# enrgymeter_-_Copy.net
KiCad netlist of a schematic drawn in EAGLE
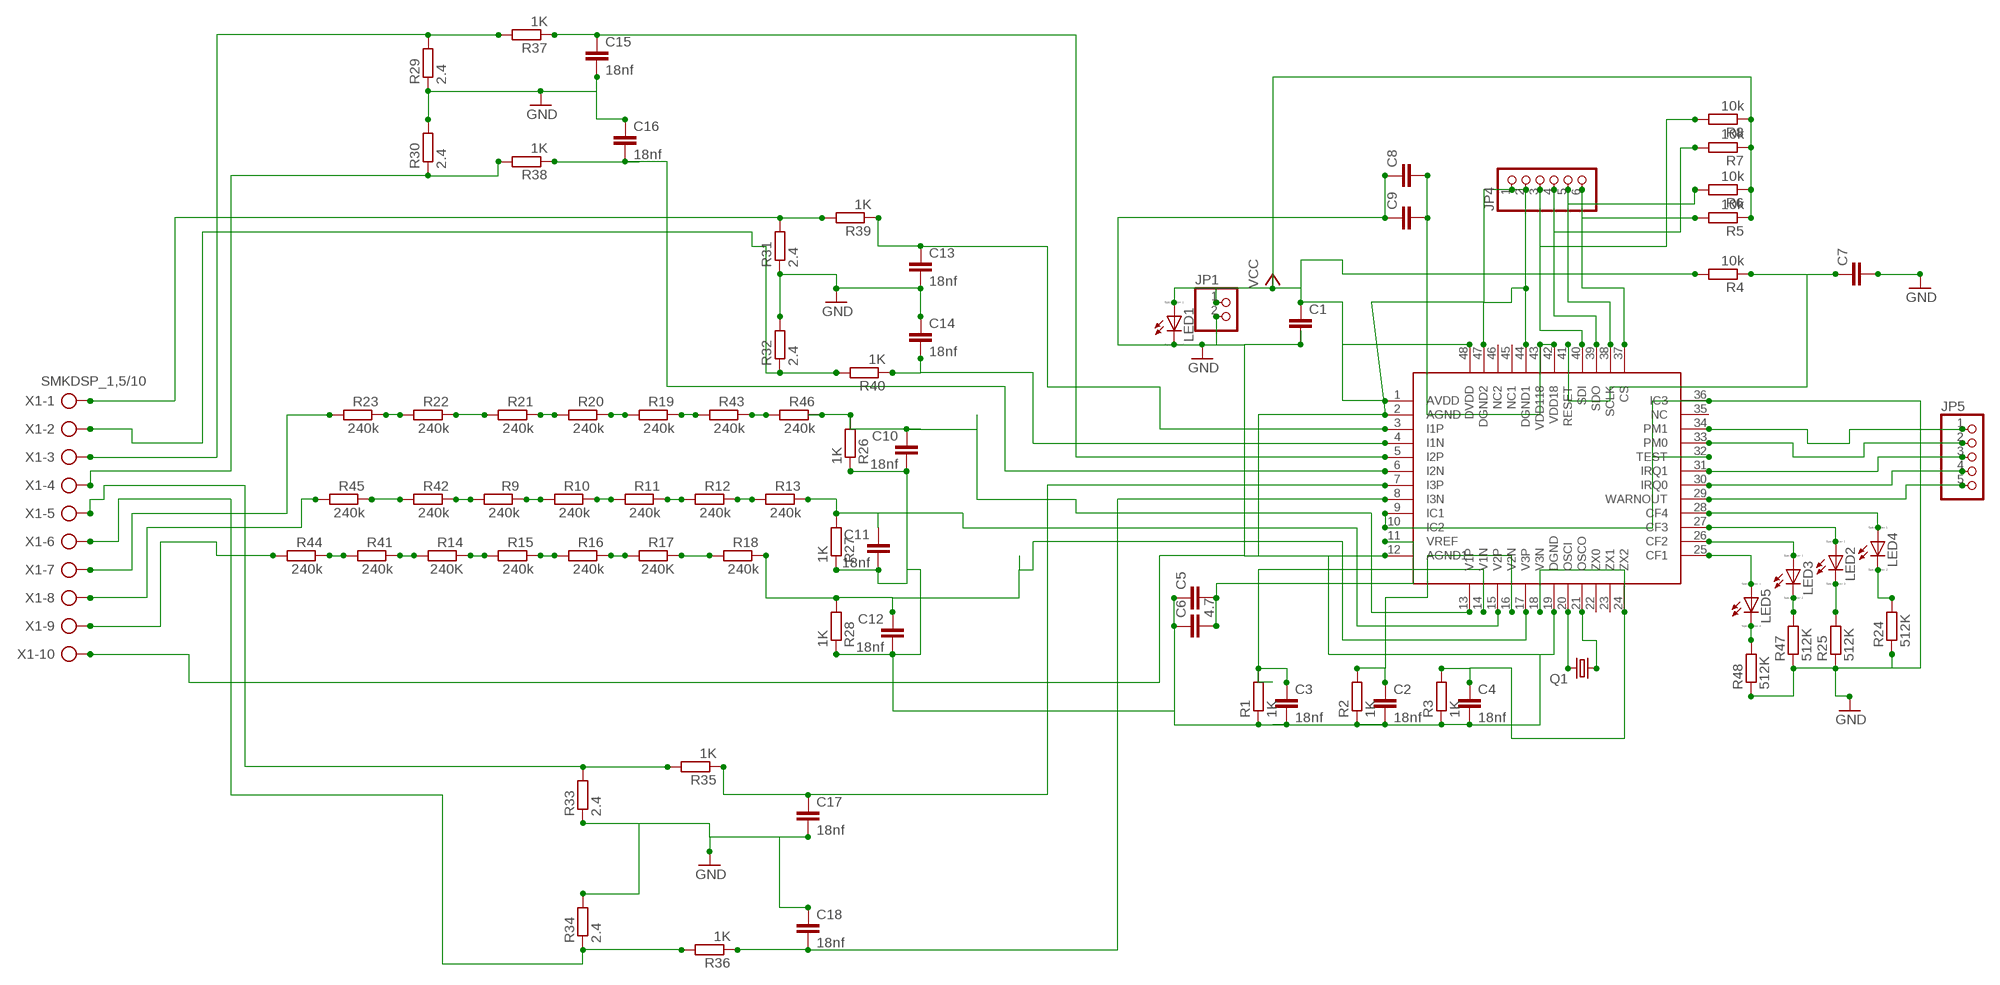
[diagram p0: schematic, sheet 1]

(export (version "E")
  (design (tool "Eeschema 10.0.6"))
  (components
    (comp (ref "C1")
      (value "C-EUC1210")
      (footprint "eagle-import:C1210")
      (libsource (lib "eagle-import") (part "C-EUC1210"))
    )
    (comp (ref "C2")
      (value "18nf")
      (footprint "eagle-import:C0402")
      (libsource (lib "eagle-import") (part "C-EUC0402"))
    )
    (comp (ref "C3")
      (value "18nf")
      (footprint "eagle-import:C0402")
      (libsource (lib "eagle-import") (part "C-EUC0402"))
    )
    (comp (ref "C4")
      (value "18nf")
      (footprint "eagle-import:C0402")
      (libsource (lib "eagle-import") (part "C-EUC0402"))
    )
    (comp (ref "C5")
      (value "C-EUC1210")
      (footprint "eagle-import:C1210")
      (libsource (lib "eagle-import") (part "C-EUC1210"))
    )
    (comp (ref "C6")
      (value "4.7")
      (footprint "eagle-import:C0805")
      (libsource (lib "eagle-import") (part "C-EUC0805"))
    )
    (comp (ref "C7")
      (value "C-EUC1210")
      (footprint "eagle-import:C1210")
      (libsource (lib "eagle-import") (part "C-EUC1210"))
    )
    (comp (ref "C8")
      (value "C-EUC1210")
      (footprint "eagle-import:C1210")
      (libsource (lib "eagle-import") (part "C-EUC1210"))
    )
    (comp (ref "C9")
      (value "C-EUC1210")
      (footprint "eagle-import:C1210")
      (libsource (lib "eagle-import") (part "C-EUC1210"))
    )
    (comp (ref "C10")
      (value "18nf")
      (footprint "eagle-import:C0402")
      (libsource (lib "eagle-import") (part "C-EUC0402"))
    )
    (comp (ref "C11")
      (value "18nf")
      (footprint "eagle-import:C0402")
      (libsource (lib "eagle-import") (part "C-EUC0402"))
    )
    (comp (ref "C12")
      (value "18nf")
      (footprint "eagle-import:C0402")
      (libsource (lib "eagle-import") (part "C-EUC0402"))
    )
    (comp (ref "C13")
      (value "18nf")
      (footprint "eagle-import:C0402")
      (libsource (lib "eagle-import") (part "C-EUC0402"))
    )
    (comp (ref "C14")
      (value "18nf")
      (footprint "eagle-import:C0402")
      (libsource (lib "eagle-import") (part "C-EUC0402"))
    )
    (comp (ref "C15")
      (value "18nf")
      (footprint "eagle-import:C0402")
      (libsource (lib "eagle-import") (part "C-EUC0402"))
    )
    (comp (ref "C16")
      (value "18nf")
      (footprint "eagle-import:C0402")
      (libsource (lib "eagle-import") (part "C-EUC0402"))
    )
    (comp (ref "C17")
      (value "18nf")
      (footprint "eagle-import:C0402")
      (libsource (lib "eagle-import") (part "C-EUC0402"))
    )
    (comp (ref "C18")
      (value "18nf")
      (footprint "eagle-import:C0402")
      (libsource (lib "eagle-import") (part "C-EUC0402"))
    )
    (comp (ref "JP1")
      (value "PINHD-1X2_2.54-SMD-90°")
      (footprint "eagle-import:1X02SMD_90")
      (libsource (lib "eagle-import") (part "PINHD-1X2_2.54-SMD-90°"))
    )
    (comp (ref "JP4")
      (value "PINHD-1X6_2.54-SMD-90°")
      (footprint "eagle-import:1X06SMD_90")
      (libsource (lib "eagle-import") (part "PINHD-1X6_2.54-SMD-90°"))
    )
    (comp (ref "JP5")
      (value "PINHD-1X5_2.54-SMD-90°")
      (footprint "eagle-import:1X05SMD_90")
      (libsource (lib "eagle-import") (part "PINHD-1X5_2.54-SMD-90°"))
    )
    (comp (ref "LED1")
      (value "LED_E")
      (footprint "eagle-import:LED_1206")
      (libsource (lib "eagle-import") (part "LED_E"))
    )
    (comp (ref "LED2")
      (value "LED_E")
      (footprint "eagle-import:LED_1206")
      (libsource (lib "eagle-import") (part "LED_E"))
    )
    (comp (ref "LED3")
      (value "LED_E")
      (footprint "eagle-import:LED_1206")
      (libsource (lib "eagle-import") (part "LED_E"))
    )
    (comp (ref "LED4")
      (value "LED_E")
      (footprint "eagle-import:LED_1206")
      (libsource (lib "eagle-import") (part "LED_E"))
    )
    (comp (ref "LED5")
      (value "LED_E")
      (footprint "eagle-import:LED_1206")
      (libsource (lib "eagle-import") (part "LED_E"))
    )
    (comp (ref "Q1")
      (value "CRYSTALSM49")
      (footprint "eagle-import:SM49")
      (libsource (lib "eagle-import") (part "CRYSTALSM49"))
    )
    (comp (ref "R1")
      (value "1K")
      (footprint "eagle-import:R2512")
      (libsource (lib "eagle-import") (part "R-EU_R2512"))
    )
    (comp (ref "R2")
      (value "1K")
      (footprint "eagle-import:R2512")
      (libsource (lib "eagle-import") (part "R-EU_R2512"))
    )
    (comp (ref "R3")
      (value "1K")
      (footprint "eagle-import:R2512")
      (libsource (lib "eagle-import") (part "R-EU_R2512"))
    )
    (comp (ref "R4")
      (value "10k")
      (footprint "eagle-import:R2512")
      (libsource (lib "eagle-import") (part "R-EU_R2512"))
    )
    (comp (ref "R5")
      (value "10k")
      (footprint "eagle-import:R2512")
      (libsource (lib "eagle-import") (part "R-EU_R2512"))
    )
    (comp (ref "R6")
      (value "10k")
      (footprint "eagle-import:R2512")
      (libsource (lib "eagle-import") (part "R-EU_R2512"))
    )
    (comp (ref "R7")
      (value "10k")
      (footprint "eagle-import:R2512")
      (libsource (lib "eagle-import") (part "R-EU_R2512"))
    )
    (comp (ref "R8")
      (value "10k")
      (footprint "eagle-import:R2512")
      (libsource (lib "eagle-import") (part "R-EU_R2512"))
    )
    (comp (ref "R9")
      (value "240k")
      (footprint "eagle-import:R2512W")
      (libsource (lib "eagle-import") (part "R-EU_R2512W"))
    )
    (comp (ref "R10")
      (value "240k")
      (footprint "eagle-import:R2512W")
      (libsource (lib "eagle-import") (part "R-EU_R2512W"))
    )
    (comp (ref "R11")
      (value "240k")
      (footprint "eagle-import:R2512W")
      (libsource (lib "eagle-import") (part "R-EU_R2512W"))
    )
    (comp (ref "R12")
      (value "240k")
      (footprint "eagle-import:R2512W")
      (libsource (lib "eagle-import") (part "R-EU_R2512W"))
    )
    (comp (ref "R13")
      (value "240k")
      (footprint "eagle-import:R2512W")
      (libsource (lib "eagle-import") (part "R-EU_R2512W"))
    )
    (comp (ref "R14")
      (value "240K")
      (footprint "eagle-import:R2512W")
      (libsource (lib "eagle-import") (part "R-EU_R2512W"))
    )
    (comp (ref "R15")
      (value "240k")
      (footprint "eagle-import:R2512W")
      (libsource (lib "eagle-import") (part "R-EU_R2512W"))
    )
    (comp (ref "R16")
      (value "240k")
      (footprint "eagle-import:R2512W")
      (libsource (lib "eagle-import") (part "R-EU_R2512W"))
    )
    (comp (ref "R17")
      (value "240K")
      (footprint "eagle-import:R2512W")
      (libsource (lib "eagle-import") (part "R-EU_R2512W"))
    )
    (comp (ref "R18")
      (value "240k")
      (footprint "eagle-import:R2512W")
      (libsource (lib "eagle-import") (part "R-EU_R2512W"))
    )
    (comp (ref "R19")
      (value "240k")
      (footprint "eagle-import:R2512W")
      (libsource (lib "eagle-import") (part "R-EU_R2512W"))
    )
    (comp (ref "R20")
      (value "240k")
      (footprint "eagle-import:R2512W")
      (libsource (lib "eagle-import") (part "R-EU_R2512W"))
    )
    (comp (ref "R21")
      (value "240k")
      (footprint "eagle-import:R2512W")
      (libsource (lib "eagle-import") (part "R-EU_R2512W"))
    )
    (comp (ref "R22")
      (value "240k")
      (footprint "eagle-import:R2512W")
      (libsource (lib "eagle-import") (part "R-EU_R2512W"))
    )
    (comp (ref "R23")
      (value "240k")
      (footprint "eagle-import:R2512W")
      (libsource (lib "eagle-import") (part "R-EU_R2512W"))
    )
    (comp (ref "R24")
      (value "512K")
      (footprint "eagle-import:R2512W")
      (libsource (lib "eagle-import") (part "R-EU_R2512W"))
    )
    (comp (ref "R25")
      (value "512K")
      (footprint "eagle-import:R2512W")
      (libsource (lib "eagle-import") (part "R-EU_R2512W"))
    )
    (comp (ref "R26")
      (value "1K")
      (footprint "eagle-import:R2512")
      (libsource (lib "eagle-import") (part "R-EU_R2512"))
    )
    (comp (ref "R27")
      (value "1K")
      (footprint "eagle-import:R2512")
      (libsource (lib "eagle-import") (part "R-EU_R2512"))
    )
    (comp (ref "R28")
      (value "1K")
      (footprint "eagle-import:R2512")
      (libsource (lib "eagle-import") (part "R-EU_R2512"))
    )
    (comp (ref "R29")
      (value "2.4")
      (footprint "eagle-import:R2512")
      (libsource (lib "eagle-import") (part "R-EU_R2512"))
    )
    (comp (ref "R30")
      (value "2.4")
      (footprint "eagle-import:R2512")
      (libsource (lib "eagle-import") (part "R-EU_R2512"))
    )
    (comp (ref "R31")
      (value "2.4")
      (footprint "eagle-import:R2512")
      (libsource (lib "eagle-import") (part "R-EU_R2512"))
    )
    (comp (ref "R32")
      (value "2.4")
      (footprint "eagle-import:R2512")
      (libsource (lib "eagle-import") (part "R-EU_R2512"))
    )
    (comp (ref "R33")
      (value "2.4")
      (footprint "eagle-import:R2512")
      (libsource (lib "eagle-import") (part "R-EU_R2512"))
    )
    (comp (ref "R34")
      (value "2.4")
      (footprint "eagle-import:R2512")
      (libsource (lib "eagle-import") (part "R-EU_R2512"))
    )
    (comp (ref "R35")
      (value "1K")
      (footprint "eagle-import:R2512")
      (libsource (lib "eagle-import") (part "R-EU_R2512"))
    )
    (comp (ref "R36")
      (value "1K")
      (footprint "eagle-import:R2512")
      (libsource (lib "eagle-import") (part "R-EU_R2512"))
    )
    (comp (ref "R37")
      (value "1K")
      (footprint "eagle-import:R2512")
      (libsource (lib "eagle-import") (part "R-EU_R2512"))
    )
    (comp (ref "R38")
      (value "1K")
      (footprint "eagle-import:R2512")
      (libsource (lib "eagle-import") (part "R-EU_R2512"))
    )
    (comp (ref "R39")
      (value "1K")
      (footprint "eagle-import:R2512")
      (libsource (lib "eagle-import") (part "R-EU_R2512"))
    )
    (comp (ref "R40")
      (value "1K")
      (footprint "eagle-import:R2512")
      (libsource (lib "eagle-import") (part "R-EU_R2512"))
    )
    (comp (ref "R41")
      (value "240k")
      (footprint "eagle-import:R2512W")
      (libsource (lib "eagle-import") (part "R-EU_R2512W"))
    )
    (comp (ref "R42")
      (value "240k")
      (footprint "eagle-import:R2512W")
      (libsource (lib "eagle-import") (part "R-EU_R2512W"))
    )
    (comp (ref "R43")
      (value "240k")
      (footprint "eagle-import:R2512W")
      (libsource (lib "eagle-import") (part "R-EU_R2512W"))
    )
    (comp (ref "R44")
      (value "240k")
      (footprint "eagle-import:R2512W")
      (libsource (lib "eagle-import") (part "R-EU_R2512W"))
    )
    (comp (ref "R45")
      (value "240k")
      (footprint "eagle-import:R2512W")
      (libsource (lib "eagle-import") (part "R-EU_R2512W"))
    )
    (comp (ref "R46")
      (value "240k")
      (footprint "eagle-import:R2512W")
      (libsource (lib "eagle-import") (part "R-EU_R2512W"))
    )
    (comp (ref "R47")
      (value "512K")
      (footprint "eagle-import:R2512W")
      (libsource (lib "eagle-import") (part "R-EU_R2512W"))
    )
    (comp (ref "R48")
      (value "512K")
      (footprint "eagle-import:R2512W")
      (libsource (lib "eagle-import") (part "R-EU_R2512W"))
    )
    (comp (ref "U$1")
      (value "M90E32AS")
      (footprint "eagle-import:M90E32AS")
      (libsource (lib "eagle-import") (part "M90E32AS"))
    )
    (comp (ref "X1")
      (value "SMKDSP_1,5/10")
      (footprint "eagle-import:SMKDSP_1,5_10")
      (fields (field (name "MF") "FARNELL") (field (name "MPN") "1733651"))
      (libsource (lib "eagle-import") (part "SMKDSP_1,5/10"))
    )
  )
  (nets
    (net (code "1") (name "GND") (class "Default")
      (node (ref "C1") (pin "2") (pinfunction "2_2") (pintype "passive"))
      (node (ref "C10") (pin "2") (pinfunction "2_2") (pintype "passive"))
      (node (ref "C11") (pin "2") (pinfunction "2_2") (pintype "passive"))
      (node (ref "C12") (pin "2") (pinfunction "2_2") (pintype "passive"))
      (node (ref "C13") (pin "2") (pinfunction "2_2") (pintype "passive"))
      (node (ref "C14") (pin "1") (pinfunction "1_1") (pintype "passive"))
      (node (ref "C15") (pin "2") (pinfunction "2_2") (pintype "passive"))
      (node (ref "C16") (pin "1") (pinfunction "1_1") (pintype "passive"))
      (node (ref "C17") (pin "2") (pinfunction "2_2") (pintype "passive"))
      (node (ref "C18") (pin "1") (pinfunction "1_1") (pintype "passive"))
      (node (ref "C2") (pin "2") (pinfunction "2_2") (pintype "passive"))
      (node (ref "C3") (pin "2") (pinfunction "2_2") (pintype "passive"))
      (node (ref "C4") (pin "2") (pinfunction "2_2") (pintype "passive"))
      (node (ref "C5") (pin "1") (pinfunction "1_1") (pintype "passive"))
      (node (ref "C6") (pin "1") (pinfunction "1_1") (pintype "passive"))
      (node (ref "C7") (pin "2") (pinfunction "2_2") (pintype "passive"))
      (node (ref "C8") (pin "1") (pinfunction "1_1") (pintype "passive"))
      (node (ref "C9") (pin "1") (pinfunction "1_1") (pintype "passive"))
      (node (ref "JP1") (pin "2") (pinfunction "2_2") (pintype "passive"))
      (node (ref "JP4") (pin "1") (pinfunction "1_1") (pintype "passive"))
      (node (ref "JP4") (pin "2") (pinfunction "2_2") (pintype "passive"))
      (node (ref "LED1") (pin "C") (pinfunction "C_C") (pintype "passive"))
      (node (ref "R1") (pin "1") (pinfunction "1_1") (pintype "passive"))
      (node (ref "R2") (pin "1") (pinfunction "1_1") (pintype "passive"))
      (node (ref "R24") (pin "1") (pinfunction "1_1") (pintype "passive"))
      (node (ref "R25") (pin "1") (pinfunction "1_1") (pintype "passive"))
      (node (ref "R26") (pin "1") (pinfunction "1_1") (pintype "passive"))
      (node (ref "R27") (pin "1") (pinfunction "1_1") (pintype "passive"))
      (node (ref "R28") (pin "1") (pinfunction "1_1") (pintype "passive"))
      (node (ref "R29") (pin "1") (pinfunction "1_1") (pintype "passive"))
      (node (ref "R3") (pin "1") (pinfunction "1_1") (pintype "passive"))
      (node (ref "R30") (pin "2") (pinfunction "2_2") (pintype "passive"))
      (node (ref "R31") (pin "1") (pinfunction "1_1") (pintype "passive"))
      (node (ref "R32") (pin "2") (pinfunction "2_2") (pintype "passive"))
      (node (ref "R33") (pin "1") (pinfunction "1_1") (pintype "passive"))
      (node (ref "R34") (pin "2") (pinfunction "2_2") (pintype "passive"))
      (node (ref "R47") (pin "1") (pinfunction "1_1") (pintype "passive"))
      (node (ref "R48") (pin "1") (pinfunction "1_1") (pintype "passive"))
      (node (ref "U$1") (pin "10") (pinfunction "IC2_10") (pintype "bidirectional"))
      (node (ref "U$1") (pin "12") (pinfunction "AGND1_12") (pintype "bidirectional"))
      (node (ref "U$1") (pin "19") (pinfunction "DGND_19") (pintype "bidirectional"))
      (node (ref "U$1") (pin "2") (pinfunction "AGND_2") (pintype "bidirectional"))
      (node (ref "U$1") (pin "32") (pinfunction "TEST_32") (pintype "bidirectional"))
      (node (ref "U$1") (pin "36") (pinfunction "IC3_36") (pintype "bidirectional"))
      (node (ref "U$1") (pin "44") (pinfunction "DGND1_44") (pintype "bidirectional"))
      (node (ref "U$1") (pin "47") (pinfunction "DGND2_47") (pintype "bidirectional"))
      (node (ref "U$1") (pin "9") (pinfunction "IC1_9") (pintype "bidirectional"))
      (node (ref "X1") (pin "10") (pinfunction "KL_10") (pintype "passive"))
    )
    (net (code "2") (name "Net-(LED2-PadC)") (class "Default")
      (node (ref "LED2") (pin "C") (pinfunction "C_C") (pintype "passive"))
      (node (ref "R25") (pin "2") (pinfunction "2_2") (pintype "passive"))
    )
    (net (code "3") (name "Net-(LED3-PadC)") (class "Default")
      (node (ref "LED3") (pin "C") (pinfunction "C_C") (pintype "passive"))
      (node (ref "R47") (pin "2") (pinfunction "2_2") (pintype "passive"))
    )
    (net (code "4") (name "Net-(LED4-PadC)") (class "Default")
      (node (ref "LED4") (pin "C") (pinfunction "C_C") (pintype "passive"))
      (node (ref "R24") (pin "2") (pinfunction "2_2") (pintype "passive"))
    )
    (net (code "5") (name "Net-(LED5-PadC)") (class "Default")
      (node (ref "LED5") (pin "C") (pinfunction "C_C") (pintype "passive"))
      (node (ref "R48") (pin "2") (pinfunction "2_2") (pintype "passive"))
    )
    (net (code "6") (name "Net-(R10-Pad1)") (class "Default")
      (node (ref "R10") (pin "1") (pinfunction "1_1") (pintype "passive"))
      (node (ref "R11") (pin "2") (pinfunction "2_2") (pintype "passive"))
    )
    (net (code "7") (name "Net-(R10-Pad2)") (class "Default")
      (node (ref "R10") (pin "2") (pinfunction "2_2") (pintype "passive"))
      (node (ref "R9") (pin "1") (pinfunction "1_1") (pintype "passive"))
    )
    (net (code "8") (name "Net-(R11-Pad1)") (class "Default")
      (node (ref "R11") (pin "1") (pinfunction "1_1") (pintype "passive"))
      (node (ref "R12") (pin "2") (pinfunction "2_2") (pintype "passive"))
    )
    (net (code "9") (name "Net-(R12-Pad1)") (class "Default")
      (node (ref "R12") (pin "1") (pinfunction "1_1") (pintype "passive"))
      (node (ref "R13") (pin "2") (pinfunction "2_2") (pintype "passive"))
    )
    (net (code "10") (name "Net-(R14-Pad1)") (class "Default")
      (node (ref "R14") (pin "1") (pinfunction "1_1") (pintype "passive"))
      (node (ref "R15") (pin "2") (pinfunction "2_2") (pintype "passive"))
    )
    (net (code "11") (name "Net-(R14-Pad2)") (class "Default")
      (node (ref "R14") (pin "2") (pinfunction "2_2") (pintype "passive"))
      (node (ref "R41") (pin "1") (pinfunction "1_1") (pintype "passive"))
    )
    (net (code "12") (name "Net-(R15-Pad1)") (class "Default")
      (node (ref "R15") (pin "1") (pinfunction "1_1") (pintype "passive"))
      (node (ref "R16") (pin "2") (pinfunction "2_2") (pintype "passive"))
    )
    (net (code "13") (name "Net-(R16-Pad1)") (class "Default")
      (node (ref "R16") (pin "1") (pinfunction "1_1") (pintype "passive"))
      (node (ref "R17") (pin "2") (pinfunction "2_2") (pintype "passive"))
    )
    (net (code "14") (name "Net-(R17-Pad1)") (class "Default")
      (node (ref "R17") (pin "1") (pinfunction "1_1") (pintype "passive"))
      (node (ref "R18") (pin "2") (pinfunction "2_2") (pintype "passive"))
    )
    (net (code "15") (name "Net-(R19-Pad1)") (class "Default")
      (node (ref "R19") (pin "1") (pinfunction "1_1") (pintype "passive"))
      (node (ref "R43") (pin "2") (pinfunction "2_2") (pintype "passive"))
    )
    (net (code "16") (name "Net-(R19-Pad2)") (class "Default")
      (node (ref "R19") (pin "2") (pinfunction "2_2") (pintype "passive"))
      (node (ref "R20") (pin "1") (pinfunction "1_1") (pintype "passive"))
    )
    (net (code "17") (name "Net-(R20-Pad2)") (class "Default")
      (node (ref "R20") (pin "2") (pinfunction "2_2") (pintype "passive"))
      (node (ref "R21") (pin "1") (pinfunction "1_1") (pintype "passive"))
    )
    (net (code "18") (name "Net-(R21-Pad2)") (class "Default")
      (node (ref "R21") (pin "2") (pinfunction "2_2") (pintype "passive"))
      (node (ref "R22") (pin "1") (pinfunction "1_1") (pintype "passive"))
    )
    (net (code "19") (name "Net-(R22-Pad2)") (class "Default")
      (node (ref "R22") (pin "2") (pinfunction "2_2") (pintype "passive"))
      (node (ref "R23") (pin "1") (pinfunction "1_1") (pintype "passive"))
    )
    (net (code "20") (name "Net-(R41-Pad2)") (class "Default")
      (node (ref "R41") (pin "2") (pinfunction "2_2") (pintype "passive"))
      (node (ref "R44") (pin "1") (pinfunction "1_1") (pintype "passive"))
    )
    (net (code "21") (name "Net-(R42-Pad1)") (class "Default")
      (node (ref "R42") (pin "1") (pinfunction "1_1") (pintype "passive"))
      (node (ref "R9") (pin "2") (pinfunction "2_2") (pintype "passive"))
    )
    (net (code "22") (name "Net-(R42-Pad2)") (class "Default")
      (node (ref "R42") (pin "2") (pinfunction "2_2") (pintype "passive"))
      (node (ref "R45") (pin "1") (pinfunction "1_1") (pintype "passive"))
    )
    (net (code "23") (name "Net-(R43-Pad1)") (class "Default")
      (node (ref "R43") (pin "1") (pinfunction "1_1") (pintype "passive"))
      (node (ref "R46") (pin "2") (pinfunction "2_2") (pintype "passive"))
    )
    (net (code "24") (name "Net-(U$1-CF1)") (class "Default")
      (node (ref "LED5") (pin "A") (pinfunction "A_A") (pintype "passive"))
      (node (ref "U$1") (pin "25") (pinfunction "CF1_25") (pintype "bidirectional"))
    )
    (net (code "25") (name "Net-(U$1-CF2)") (class "Default")
      (node (ref "LED3") (pin "A") (pinfunction "A_A") (pintype "passive"))
      (node (ref "U$1") (pin "26") (pinfunction "CF2_26") (pintype "bidirectional"))
    )
    (net (code "26") (name "Net-(U$1-CF3)") (class "Default")
      (node (ref "LED2") (pin "A") (pinfunction "A_A") (pintype "passive"))
      (node (ref "U$1") (pin "27") (pinfunction "CF3_27") (pintype "bidirectional"))
    )
    (net (code "27") (name "Net-(U$1-CF4)") (class "Default")
      (node (ref "LED4") (pin "A") (pinfunction "A_A") (pintype "passive"))
      (node (ref "U$1") (pin "28") (pinfunction "CF4_28") (pintype "bidirectional"))
    )
    (net (code "28") (name "Net-(U$1-CS)") (class "Default")
      (node (ref "JP4") (pin "6") (pinfunction "6_6") (pintype "passive"))
      (node (ref "R5") (pin "2") (pinfunction "2_2") (pintype "passive"))
      (node (ref "U$1") (pin "37") (pinfunction "CS_37") (pintype "bidirectional"))
    )
    (net (code "29") (name "Net-(U$1-I1N)") (class "Default")
      (node (ref "C14") (pin "2") (pinfunction "2_2") (pintype "passive"))
      (node (ref "R40") (pin "1") (pinfunction "1_1") (pintype "passive"))
      (node (ref "U$1") (pin "4") (pinfunction "I1N_4") (pintype "bidirectional"))
    )
    (net (code "30") (name "Net-(U$1-I1P)") (class "Default")
      (node (ref "C13") (pin "1") (pinfunction "1_1") (pintype "passive"))
      (node (ref "R39") (pin "1") (pinfunction "1_1") (pintype "passive"))
      (node (ref "U$1") (pin "3") (pinfunction "I1P_3") (pintype "bidirectional"))
    )
    (net (code "31") (name "Net-(U$1-I2N)") (class "Default")
      (node (ref "C16") (pin "2") (pinfunction "2_2") (pintype "passive"))
      (node (ref "R38") (pin "1") (pinfunction "1_1") (pintype "passive"))
      (node (ref "U$1") (pin "6") (pinfunction "I2N_6") (pintype "bidirectional"))
    )
    (net (code "32") (name "Net-(U$1-I2P)") (class "Default")
      (node (ref "C15") (pin "1") (pinfunction "1_1") (pintype "passive"))
      (node (ref "R37") (pin "1") (pinfunction "1_1") (pintype "passive"))
      (node (ref "U$1") (pin "5") (pinfunction "I2P_5") (pintype "bidirectional"))
    )
    (net (code "33") (name "Net-(U$1-I3N)") (class "Default")
      (node (ref "C18") (pin "2") (pinfunction "2_2") (pintype "passive"))
      (node (ref "R36") (pin "1") (pinfunction "1_1") (pintype "passive"))
      (node (ref "U$1") (pin "8") (pinfunction "I3N_8") (pintype "bidirectional"))
    )
    (net (code "34") (name "Net-(U$1-I3P)") (class "Default")
      (node (ref "C17") (pin "1") (pinfunction "1_1") (pintype "passive"))
      (node (ref "R35") (pin "1") (pinfunction "1_1") (pintype "passive"))
      (node (ref "U$1") (pin "7") (pinfunction "I3P_7") (pintype "bidirectional"))
    )
    (net (code "35") (name "Net-(U$1-IRQ0)") (class "Default")
      (node (ref "JP5") (pin "4") (pinfunction "4_4") (pintype "passive"))
      (node (ref "U$1") (pin "30") (pinfunction "IRQ0_30") (pintype "bidirectional"))
    )
    (net (code "36") (name "Net-(U$1-IRQ1)") (class "Default")
      (node (ref "JP5") (pin "3") (pinfunction "3_3") (pintype "passive"))
      (node (ref "U$1") (pin "31") (pinfunction "IRQ1_31") (pintype "bidirectional"))
    )
    (net (code "37") (name "Net-(U$1-OSCI)") (class "Default")
      (node (ref "Q1") (pin "2") (pinfunction "2_2") (pintype "passive"))
      (node (ref "U$1") (pin "20") (pinfunction "OSCI_20") (pintype "bidirectional"))
    )
    (net (code "38") (name "Net-(U$1-OSCO)") (class "Default")
      (node (ref "Q1") (pin "1") (pinfunction "1_1") (pintype "passive"))
      (node (ref "U$1") (pin "21") (pinfunction "OSCO_21") (pintype "bidirectional"))
    )
    (net (code "39") (name "Net-(U$1-PM0)") (class "Default")
      (node (ref "JP5") (pin "2") (pinfunction "2_2") (pintype "passive"))
      (node (ref "U$1") (pin "33") (pinfunction "PM0_33") (pintype "bidirectional"))
    )
    (net (code "40") (name "Net-(U$1-PM1)") (class "Default")
      (node (ref "JP5") (pin "1") (pinfunction "1_1") (pintype "passive"))
      (node (ref "U$1") (pin "34") (pinfunction "PM1_34") (pintype "bidirectional"))
    )
    (net (code "41") (name "Net-(U$1-RESET)") (class "Default")
      (node (ref "C7") (pin "1") (pinfunction "1_1") (pintype "passive"))
      (node (ref "R4") (pin "1") (pinfunction "1_1") (pintype "passive"))
      (node (ref "U$1") (pin "41") (pinfunction "RESET_41") (pintype "bidirectional"))
    )
    (net (code "42") (name "Net-(U$1-SCLK)") (class "Default")
      (node (ref "JP4") (pin "5") (pinfunction "5_5") (pintype "passive"))
      (node (ref "R6") (pin "2") (pinfunction "2_2") (pintype "passive"))
      (node (ref "U$1") (pin "38") (pinfunction "SCLK_38") (pintype "bidirectional"))
    )
    (net (code "43") (name "Net-(U$1-SDI)") (class "Default")
      (node (ref "JP4") (pin "3") (pinfunction "3_3") (pintype "passive"))
      (node (ref "R8") (pin "2") (pinfunction "2_2") (pintype "passive"))
      (node (ref "U$1") (pin "40") (pinfunction "SDI_40") (pintype "bidirectional"))
    )
    (net (code "44") (name "Net-(U$1-SDO)") (class "Default")
      (node (ref "JP4") (pin "4") (pinfunction "4_4") (pintype "passive"))
      (node (ref "R7") (pin "2") (pinfunction "2_2") (pintype "passive"))
      (node (ref "U$1") (pin "39") (pinfunction "SDO_39") (pintype "bidirectional"))
    )
    (net (code "45") (name "Net-(U$1-V1N)") (class "Default")
      (node (ref "C3") (pin "1") (pinfunction "1_1") (pintype "passive"))
      (node (ref "R1") (pin "2") (pinfunction "2_2") (pintype "passive"))
      (node (ref "U$1") (pin "14") (pinfunction "V1N_14") (pintype "bidirectional"))
    )
    (net (code "46") (name "Net-(U$1-V1P)") (class "Default")
      (node (ref "C10") (pin "1") (pinfunction "1_1") (pintype "passive"))
      (node (ref "R26") (pin "2") (pinfunction "2_2") (pintype "passive"))
      (node (ref "R46") (pin "1") (pinfunction "1_1") (pintype "passive"))
      (node (ref "U$1") (pin "13") (pinfunction "V1P_13") (pintype "bidirectional"))
    )
    (net (code "47") (name "Net-(U$1-V2N)") (class "Default")
      (node (ref "C2") (pin "1") (pinfunction "1_1") (pintype "passive"))
      (node (ref "R2") (pin "2") (pinfunction "2_2") (pintype "passive"))
      (node (ref "U$1") (pin "16") (pinfunction "V2N_16") (pintype "bidirectional"))
    )
    (net (code "48") (name "Net-(U$1-V2P)") (class "Default")
      (node (ref "C11") (pin "1") (pinfunction "1_1") (pintype "passive"))
      (node (ref "R13") (pin "1") (pinfunction "1_1") (pintype "passive"))
      (node (ref "R27") (pin "2") (pinfunction "2_2") (pintype "passive"))
      (node (ref "U$1") (pin "15") (pinfunction "V2P_15") (pintype "bidirectional"))
    )
    (net (code "49") (name "Net-(U$1-V3N)") (class "Default")
      (node (ref "C4") (pin "1") (pinfunction "1_1") (pintype "passive"))
      (node (ref "R3") (pin "2") (pinfunction "2_2") (pintype "passive"))
      (node (ref "U$1") (pin "18") (pinfunction "V3N_18") (pintype "bidirectional"))
      (node (ref "U$1") (pin "24") (pinfunction "ZX2_24") (pintype "bidirectional"))
    )
    (net (code "50") (name "Net-(U$1-V3P)") (class "Default")
      (node (ref "C12") (pin "1") (pinfunction "1_1") (pintype "passive"))
      (node (ref "R18") (pin "1") (pinfunction "1_1") (pintype "passive"))
      (node (ref "R28") (pin "2") (pinfunction "2_2") (pintype "passive"))
      (node (ref "U$1") (pin "17") (pinfunction "V3P_17") (pintype "bidirectional"))
    )
    (net (code "51") (name "Net-(U$1-VDD118)") (class "Default")
      (node (ref "C8") (pin "2") (pinfunction "2_2") (pintype "passive"))
      (node (ref "C9") (pin "2") (pinfunction "2_2") (pintype "passive"))
      (node (ref "U$1") (pin "42") (pinfunction "VDD18_42") (pintype "bidirectional"))
      (node (ref "U$1") (pin "43") (pinfunction "VDD118_43") (pintype "bidirectional"))
    )
    (net (code "52") (name "Net-(U$1-VREF)") (class "Default")
      (node (ref "C5") (pin "2") (pinfunction "2_2") (pintype "passive"))
      (node (ref "C6") (pin "2") (pinfunction "2_2") (pintype "passive"))
      (node (ref "U$1") (pin "11") (pinfunction "VREF_11") (pintype "bidirectional"))
    )
    (net (code "53") (name "Net-(U$1-WARNOUT)") (class "Default")
      (node (ref "JP5") (pin "5") (pinfunction "5_5") (pintype "passive"))
      (node (ref "U$1") (pin "29") (pinfunction "WARNOUT_29") (pintype "bidirectional"))
    )
    (net (code "54") (name "Net-(X1A-KL)") (class "Default")
      (node (ref "R31") (pin "2") (pinfunction "2_2") (pintype "passive"))
      (node (ref "R39") (pin "2") (pinfunction "2_2") (pintype "passive"))
      (node (ref "X1") (pin "1") (pinfunction "KL_1") (pintype "passive"))
    )
    (net (code "55") (name "Net-(X1C-KL)") (class "Default")
      (node (ref "R32") (pin "1") (pinfunction "1_1") (pintype "passive"))
      (node (ref "R40") (pin "2") (pinfunction "2_2") (pintype "passive"))
      (node (ref "X1") (pin "2") (pinfunction "KL_2") (pintype "passive"))
    )
    (net (code "56") (name "Net-(X1D-KL)") (class "Default")
      (node (ref "R29") (pin "2") (pinfunction "2_2") (pintype "passive"))
      (node (ref "R37") (pin "2") (pinfunction "2_2") (pintype "passive"))
      (node (ref "X1") (pin "3") (pinfunction "KL_3") (pintype "passive"))
    )
    (net (code "57") (name "Net-(X1E-KL)") (class "Default")
      (node (ref "R30") (pin "1") (pinfunction "1_1") (pintype "passive"))
      (node (ref "R38") (pin "2") (pinfunction "2_2") (pintype "passive"))
      (node (ref "X1") (pin "4") (pinfunction "KL_4") (pintype "passive"))
    )
    (net (code "58") (name "Net-(X1F-KL)") (class "Default")
      (node (ref "R33") (pin "2") (pinfunction "2_2") (pintype "passive"))
      (node (ref "R35") (pin "2") (pinfunction "2_2") (pintype "passive"))
      (node (ref "X1") (pin "5") (pinfunction "KL_5") (pintype "passive"))
    )
    (net (code "59") (name "Net-(X1G-KL)") (class "Default")
      (node (ref "R34") (pin "1") (pinfunction "1_1") (pintype "passive"))
      (node (ref "R36") (pin "2") (pinfunction "2_2") (pintype "passive"))
      (node (ref "X1") (pin "6") (pinfunction "KL_6") (pintype "passive"))
    )
    (net (code "60") (name "Net-(X1H-KL)") (class "Default")
      (node (ref "R23") (pin "2") (pinfunction "2_2") (pintype "passive"))
      (node (ref "X1") (pin "7") (pinfunction "KL_7") (pintype "passive"))
    )
    (net (code "61") (name "Net-(X1I-KL)") (class "Default")
      (node (ref "R45") (pin "2") (pinfunction "2_2") (pintype "passive"))
      (node (ref "X1") (pin "8") (pinfunction "KL_8") (pintype "passive"))
    )
    (net (code "62") (name "Net-(X1J-KL)") (class "Default")
      (node (ref "R44") (pin "2") (pinfunction "2_2") (pintype "passive"))
      (node (ref "X1") (pin "9") (pinfunction "KL_9") (pintype "passive"))
    )
    (net (code "63") (name "VCC") (class "Default")
      (node (ref "C1") (pin "1") (pinfunction "1_1") (pintype "passive"))
      (node (ref "JP1") (pin "1") (pinfunction "1_1") (pintype "passive"))
      (node (ref "LED1") (pin "A") (pinfunction "A_A") (pintype "passive"))
      (node (ref "R4") (pin "2") (pinfunction "2_2") (pintype "passive"))
      (node (ref "R5") (pin "1") (pinfunction "1_1") (pintype "passive"))
      (node (ref "R6") (pin "1") (pinfunction "1_1") (pintype "passive"))
      (node (ref "R7") (pin "1") (pinfunction "1_1") (pintype "passive"))
      (node (ref "R8") (pin "1") (pinfunction "1_1") (pintype "passive"))
      (node (ref "U$1") (pin "1") (pinfunction "AVDD_1") (pintype "bidirectional"))
      (node (ref "U$1") (pin "48") (pinfunction "DVDD_48") (pintype "bidirectional"))
    )
    (net (code "64") (name "unconnected-(U$1-NC-Pad35)") (class "Default")
      (node (ref "U$1") (pin "35") (pinfunction "NC_35") (pintype "bidirectional"))
    )
    (net (code "65") (name "unconnected-(U$1-NC1-Pad45)") (class "Default")
      (node (ref "U$1") (pin "45") (pinfunction "NC1_45") (pintype "bidirectional"))
    )
    (net (code "66") (name "unconnected-(U$1-NC2-Pad46)") (class "Default")
      (node (ref "U$1") (pin "46") (pinfunction "NC2_46") (pintype "bidirectional"))
    )
    (net (code "67") (name "unconnected-(U$1-ZX0-Pad22)") (class "Default")
      (node (ref "U$1") (pin "22") (pinfunction "ZX0_22") (pintype "bidirectional"))
    )
    (net (code "68") (name "unconnected-(U$1-ZX1-Pad23)") (class "Default")
      (node (ref "U$1") (pin "23") (pinfunction "ZX1_23") (pintype "bidirectional"))
    )
  )
)
